# backpower_eeprom_rpibout.net
KiCad netlist of a schematic drawn in EAGLE
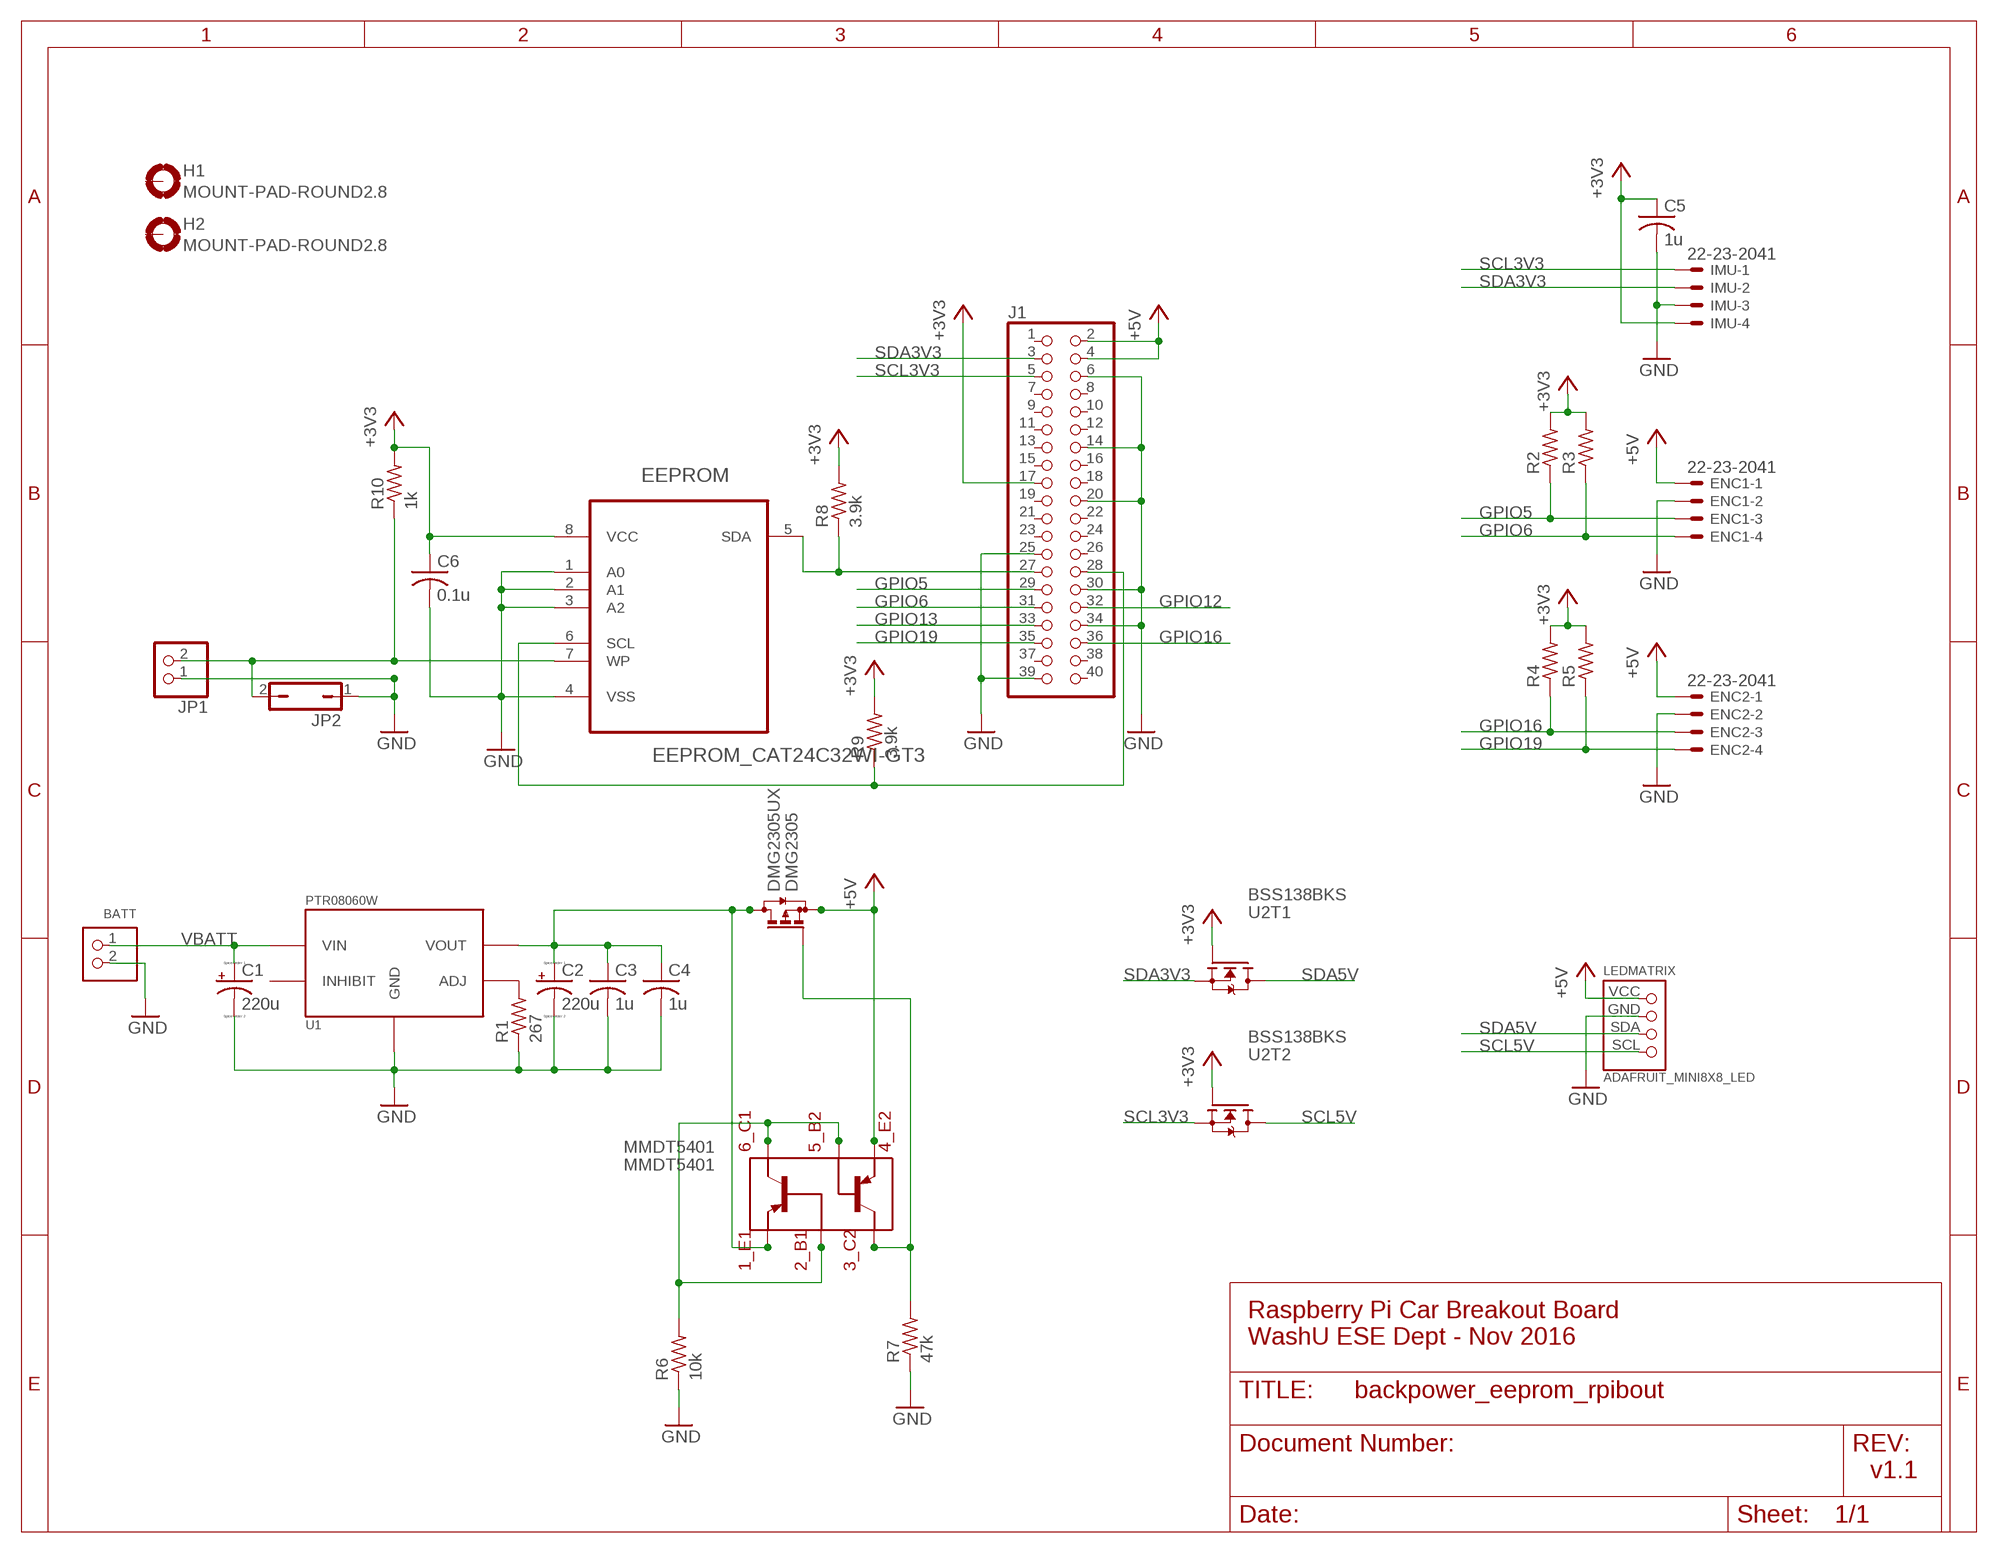
[diagram p0: schematic, sheet 1]

(export (version "E")
  (design (tool "Eeschema 10.0.6"))
  (components
    (comp (ref "BATT")
      (value "ULTRAFIT_2CIRC")
      (footprint "eagle-import:ULTRAFIT_2CIRC_RANGLE")
      (libsource (lib "eagle-import") (part "ULTRAFIT_2CIRC"))
    )
    (comp (ref "C1")
      (value "220u")
      (footprint "eagle-import:E3,5-8")
      (libsource (lib "eagle-import") (part "CPOL-USE3.5-8"))
    )
    (comp (ref "C2")
      (value "220u")
      (footprint "eagle-import:E3,5-8")
      (libsource (lib "eagle-import") (part "CPOL-USE3.5-8"))
    )
    (comp (ref "C3")
      (value "1u")
      (footprint "eagle-import:C1206")
      (libsource (lib "eagle-import") (part "C-USC1206"))
    )
    (comp (ref "C4")
      (value "1u")
      (footprint "eagle-import:C1206")
      (libsource (lib "eagle-import") (part "C-USC1206"))
    )
    (comp (ref "C5")
      (value "1u")
      (footprint "eagle-import:C1206")
      (libsource (lib "eagle-import") (part "C-USC1206"))
    )
    (comp (ref "C6")
      (value "0.1u")
      (footprint "eagle-import:C1206")
      (libsource (lib "eagle-import") (part "C-USC1206"))
    )
    (comp (ref "DMG2305")
      (value "DMG2305UX")
      (footprint "eagle-import:SOT23-3")
      (libsource (lib "eagle-import") (part "DMG2305UX"))
    )
    (comp (ref "EEPROM")
      (value "EEPROM_CAT24C32WI-GT3")
      (footprint "eagle-import:SOIC-8")
      (libsource (lib "eagle-import") (part "EEPROM_CAT24C32WI-GT3"))
    )
    (comp (ref "ENC1")
      (value "22-23-2041")
      (footprint "eagle-import:22-23-2041")
      (fields (field (name "MF") "MOLEX"))
      (libsource (lib "eagle-import") (part "22-23-2041"))
    )
    (comp (ref "ENC2")
      (value "22-23-2041")
      (footprint "eagle-import:22-23-2041")
      (fields (field (name "MF") "MOLEX"))
      (libsource (lib "eagle-import") (part "22-23-2041"))
    )
    (comp (ref "H1")
      (value "MOUNT-PAD-ROUND2.8")
      (footprint "eagle-import:2,8-PAD")
      (libsource (lib "eagle-import") (part "MOUNT-PAD-ROUND2.8"))
    )
    (comp (ref "H2")
      (value "MOUNT-PAD-ROUND2.8")
      (footprint "eagle-import:2,8-PAD")
      (libsource (lib "eagle-import") (part "MOUNT-PAD-ROUND2.8"))
    )
    (comp (ref "IMU")
      (value "22-23-2041")
      (footprint "eagle-import:22-23-2041")
      (fields (field (name "MF") "MOLEX"))
      (libsource (lib "eagle-import") (part "22-23-2041"))
    )
    (comp (ref "J1")
      (value "PINHD-2X20")
      (footprint "eagle-import:2X20")
      (libsource (lib "eagle-import") (part "PINHD-2X20"))
    )
    (comp (ref "JP1")
      (value "PINHD-1X2")
      (footprint "eagle-import:1X02")
      (libsource (lib "eagle-import") (part "PINHD-1X2"))
    )
    (comp (ref "JP2")
      (value "JP1Q")
      (footprint "eagle-import:JP1")
      (libsource (lib "eagle-import") (part "JP1Q"))
    )
    (comp (ref "LEDMATRIX")
      (value "ADAFRUIT_MINI8X8_LED")
      (footprint "eagle-import:ADAFRUIT_MINI8X8_BACKPACK")
      (libsource (lib "eagle-import") (part "ADAFRUIT_MINI8X8_LED"))
    )
    (comp (ref "MMDT5401")
      (value "MMDT5401")
      (footprint "eagle-import:SOT363")
      (libsource (lib "eagle-import") (part "MMDT5401"))
    )
    (comp (ref "R1")
      (value "267")
      (footprint "eagle-import:R1206")
      (libsource (lib "eagle-import") (part "R-US_R1206"))
    )
    (comp (ref "R2")
      (value "R-US_R1206")
      (footprint "eagle-import:R1206")
      (libsource (lib "eagle-import") (part "R-US_R1206"))
    )
    (comp (ref "R3")
      (value "R-US_R1206")
      (footprint "eagle-import:R1206")
      (libsource (lib "eagle-import") (part "R-US_R1206"))
    )
    (comp (ref "R4")
      (value "R-US_R1206")
      (footprint "eagle-import:R1206")
      (libsource (lib "eagle-import") (part "R-US_R1206"))
    )
    (comp (ref "R5")
      (value "R-US_R1206")
      (footprint "eagle-import:R1206")
      (libsource (lib "eagle-import") (part "R-US_R1206"))
    )
    (comp (ref "R6")
      (value "10k")
      (footprint "eagle-import:R1206")
      (libsource (lib "eagle-import") (part "R-US_R1206"))
    )
    (comp (ref "R7")
      (value "47k")
      (footprint "eagle-import:R1206")
      (libsource (lib "eagle-import") (part "R-US_R1206"))
    )
    (comp (ref "R8")
      (value "3.9k")
      (footprint "eagle-import:R1206")
      (libsource (lib "eagle-import") (part "R-US_R1206"))
    )
    (comp (ref "R9")
      (value "3.9k")
      (footprint "eagle-import:R1206")
      (libsource (lib "eagle-import") (part "R-US_R1206"))
    )
    (comp (ref "R10")
      (value "1k")
      (footprint "eagle-import:R1206")
      (libsource (lib "eagle-import") (part "R-US_R1206"))
    )
    (comp (ref "U1")
      (value "PTR08060W")
      (footprint "eagle-import:EDP_MODULE")
      (libsource (lib "eagle-import") (part "PTR08060W"))
    )
    (comp (ref "U2")
      (value "BSS138BKS")
      (footprint "eagle-import:SOT363")
      (libsource (lib "eagle-import") (part "BSS138BKS"))
    )
  )
  (nets
    (net (code "1") (name "+3V3") (class "Default")
      (node (ref "C5") (pin "1") (pinfunction "1_1") (pintype "passive"))
      (node (ref "C6") (pin "1") (pinfunction "1_1") (pintype "passive"))
      (node (ref "EEPROM") (pin "8") (pinfunction "VCC_8") (pintype "power_in"))
      (node (ref "IMU") (pin "4") (pinfunction "S_4") (pintype "passive"))
      (node (ref "J1") (pin "17") (pinfunction "17_17") (pintype "passive"))
      (node (ref "R10") (pin "2") (pinfunction "2_2") (pintype "passive"))
      (node (ref "R2") (pin "2") (pinfunction "2_2") (pintype "passive"))
      (node (ref "R3") (pin "2") (pinfunction "2_2") (pintype "passive"))
      (node (ref "R4") (pin "2") (pinfunction "2_2") (pintype "passive"))
      (node (ref "R5") (pin "2") (pinfunction "2_2") (pintype "passive"))
      (node (ref "R8") (pin "2") (pinfunction "2_2") (pintype "passive"))
      (node (ref "R9") (pin "2") (pinfunction "2_2") (pintype "passive"))
      (node (ref "U2") (pin "2") (pinfunction "G_2") (pintype "passive"))
      (node (ref "U2") (pin "5") (pinfunction "G_5") (pintype "passive"))
    )
    (net (code "2") (name "+5V") (class "Default")
      (node (ref "DMG2305") (pin "2") (pinfunction "S_2") (pintype "passive"))
      (node (ref "ENC1") (pin "1") (pinfunction "S_1") (pintype "passive"))
      (node (ref "ENC2") (pin "1") (pinfunction "S_1") (pintype "passive"))
      (node (ref "J1") (pin "2") (pinfunction "2_2") (pintype "passive"))
      (node (ref "J1") (pin "4") (pinfunction "4_4") (pintype "passive"))
      (node (ref "LEDMATRIX") (pin "VCC") (pinfunction "VCC_VCC") (pintype "power_in"))
      (node (ref "MMDT5401") (pin "1") (pinfunction "E1_1") (pintype "passive"))
    )
    (net (code "3") (name "/GPIO5") (class "Default")
      (node (ref "ENC1") (pin "3") (pinfunction "S_3") (pintype "passive"))
      (node (ref "J1") (pin "29") (pinfunction "29_29") (pintype "passive"))
      (node (ref "R2") (pin "1") (pinfunction "1_1") (pintype "passive"))
    )
    (net (code "4") (name "/GPIO6") (class "Default")
      (node (ref "ENC1") (pin "4") (pinfunction "S_4") (pintype "passive"))
      (node (ref "J1") (pin "31") (pinfunction "31_31") (pintype "passive"))
      (node (ref "R3") (pin "1") (pinfunction "1_1") (pintype "passive"))
    )
    (net (code "5") (name "/GPIO12") (class "Default")
      (node (ref "J1") (pin "32") (pinfunction "32_32") (pintype "passive"))
    )
    (net (code "6") (name "/GPIO13") (class "Default")
      (node (ref "J1") (pin "33") (pinfunction "33_33") (pintype "passive"))
    )
    (net (code "7") (name "/GPIO16") (class "Default")
      (node (ref "ENC2") (pin "3") (pinfunction "S_3") (pintype "passive"))
      (node (ref "J1") (pin "36") (pinfunction "36_36") (pintype "passive"))
      (node (ref "R4") (pin "1") (pinfunction "1_1") (pintype "passive"))
    )
    (net (code "8") (name "/GPIO19") (class "Default")
      (node (ref "ENC2") (pin "4") (pinfunction "S_4") (pintype "passive"))
      (node (ref "J1") (pin "35") (pinfunction "35_35") (pintype "passive"))
      (node (ref "R5") (pin "1") (pinfunction "1_1") (pintype "passive"))
    )
    (net (code "9") (name "/SCL3V3") (class "Default")
      (node (ref "IMU") (pin "1") (pinfunction "S_1") (pintype "passive"))
      (node (ref "J1") (pin "5") (pinfunction "5_5") (pintype "passive"))
      (node (ref "U2") (pin "4") (pinfunction "S_4") (pintype "passive"))
    )
    (net (code "10") (name "/SCL5V") (class "Default")
      (node (ref "LEDMATRIX") (pin "SCL") (pinfunction "SCL_SCL") (pintype "bidirectional"))
      (node (ref "U2") (pin "3") (pinfunction "D_3") (pintype "passive"))
    )
    (net (code "11") (name "/SDA3V3") (class "Default")
      (node (ref "IMU") (pin "2") (pinfunction "S_2") (pintype "passive"))
      (node (ref "J1") (pin "3") (pinfunction "3_3") (pintype "passive"))
      (node (ref "U2") (pin "1") (pinfunction "S_1") (pintype "passive"))
    )
    (net (code "12") (name "/SDA5V") (class "Default")
      (node (ref "LEDMATRIX") (pin "SDA") (pinfunction "SDA_SDA") (pintype "bidirectional"))
      (node (ref "U2") (pin "6") (pinfunction "D_6") (pintype "passive"))
    )
    (net (code "13") (name "/VBATT") (class "Default")
      (node (ref "BATT") (pin "1") (pinfunction "P1_1") (pintype "power_in"))
      (node (ref "C1") (pin "+") (pinfunction "+_+") (pintype "passive"))
      (node (ref "U1") (pin "P2") (pinfunction "VIN_P2") (pintype "power_in"))
    )
    (net (code "14") (name "GND") (class "Default")
      (node (ref "BATT") (pin "2") (pinfunction "P2_2") (pintype "power_in"))
      (node (ref "C1") (pin "-") (pinfunction "-_-") (pintype "passive"))
      (node (ref "C2") (pin "-") (pinfunction "-_-") (pintype "passive"))
      (node (ref "C3") (pin "2") (pinfunction "2_2") (pintype "passive"))
      (node (ref "C4") (pin "2") (pinfunction "2_2") (pintype "passive"))
      (node (ref "C5") (pin "2") (pinfunction "2_2") (pintype "passive"))
      (node (ref "C6") (pin "2") (pinfunction "2_2") (pintype "passive"))
      (node (ref "EEPROM") (pin "1") (pinfunction "A0_1") (pintype "input"))
      (node (ref "EEPROM") (pin "2") (pinfunction "A1_2") (pintype "input"))
      (node (ref "EEPROM") (pin "3") (pinfunction "A2_3") (pintype "input"))
      (node (ref "EEPROM") (pin "4") (pinfunction "VSS_4") (pintype "passive"))
      (node (ref "ENC1") (pin "2") (pinfunction "S_2") (pintype "passive"))
      (node (ref "ENC2") (pin "2") (pinfunction "S_2") (pintype "passive"))
      (node (ref "IMU") (pin "3") (pinfunction "S_3") (pintype "passive"))
      (node (ref "J1") (pin "14") (pinfunction "14_14") (pintype "passive"))
      (node (ref "J1") (pin "20") (pinfunction "20_20") (pintype "passive"))
      (node (ref "J1") (pin "25") (pinfunction "25_25") (pintype "passive"))
      (node (ref "J1") (pin "30") (pinfunction "30_30") (pintype "passive"))
      (node (ref "J1") (pin "34") (pinfunction "34_34") (pintype "passive"))
      (node (ref "J1") (pin "39") (pinfunction "39_39") (pintype "passive"))
      (node (ref "J1") (pin "6") (pinfunction "6_6") (pintype "passive"))
      (node (ref "JP1") (pin "1") (pinfunction "1_1") (pintype "passive"))
      (node (ref "JP2") (pin "1") (pinfunction "1_1") (pintype "passive"))
      (node (ref "LEDMATRIX") (pin "GND") (pinfunction "GND_GND") (pintype "power_in"))
      (node (ref "R1") (pin "1") (pinfunction "1_1") (pintype "passive"))
      (node (ref "R6") (pin "1") (pinfunction "1_1") (pintype "passive"))
      (node (ref "R7") (pin "1") (pinfunction "1_1") (pintype "passive"))
      (node (ref "U1") (pin "P3") (pinfunction "GND_P3") (pintype "power_in"))
    )
    (net (code "15") (name "Net-(DMG2305-D)") (class "Default")
      (node (ref "C2") (pin "+") (pinfunction "+_+") (pintype "passive"))
      (node (ref "C3") (pin "1") (pinfunction "1_1") (pintype "passive"))
      (node (ref "C4") (pin "1") (pinfunction "1_1") (pintype "passive"))
      (node (ref "DMG2305") (pin "3") (pinfunction "D_3") (pintype "passive"))
      (node (ref "MMDT5401") (pin "4") (pinfunction "E2_4") (pintype "passive"))
      (node (ref "U1") (pin "P4") (pinfunction "VOUT_P4") (pintype "power_in"))
    )
    (net (code "16") (name "Net-(DMG2305-G)") (class "Default")
      (node (ref "DMG2305") (pin "1") (pinfunction "G_1") (pintype "passive"))
      (node (ref "MMDT5401") (pin "6") (pinfunction "C1_6") (pintype "passive"))
      (node (ref "R7") (pin "2") (pinfunction "2_2") (pintype "passive"))
    )
    (net (code "17") (name "Net-(EEPROM-SCL)") (class "Default")
      (node (ref "EEPROM") (pin "6") (pinfunction "SCL_6") (pintype "input"))
      (node (ref "J1") (pin "28") (pinfunction "28_28") (pintype "passive"))
      (node (ref "R9") (pin "1") (pinfunction "1_1") (pintype "passive"))
    )
    (net (code "18") (name "Net-(EEPROM-SDA)") (class "Default")
      (node (ref "EEPROM") (pin "5") (pinfunction "SDA_5") (pintype "bidirectional"))
      (node (ref "J1") (pin "27") (pinfunction "27_27") (pintype "passive"))
      (node (ref "R8") (pin "1") (pinfunction "1_1") (pintype "passive"))
    )
    (net (code "19") (name "Net-(EEPROM-WP)") (class "Default")
      (node (ref "EEPROM") (pin "7") (pinfunction "WP_7") (pintype "input"))
      (node (ref "JP1") (pin "2") (pinfunction "2_2") (pintype "passive"))
      (node (ref "JP2") (pin "2") (pinfunction "2_2") (pintype "passive"))
      (node (ref "R10") (pin "1") (pinfunction "1_1") (pintype "passive"))
    )
    (net (code "20") (name "Net-(MMDT5401-B1)") (class "Default")
      (node (ref "MMDT5401") (pin "2") (pinfunction "B1_2") (pintype "passive"))
      (node (ref "MMDT5401") (pin "3") (pinfunction "C2_3") (pintype "passive"))
      (node (ref "MMDT5401") (pin "5") (pinfunction "B2_5") (pintype "passive"))
      (node (ref "R6") (pin "2") (pinfunction "2_2") (pintype "passive"))
    )
    (net (code "21") (name "Net-(U1-ADJ)") (class "Default")
      (node (ref "R1") (pin "2") (pinfunction "2_2") (pintype "passive"))
      (node (ref "U1") (pin "P5") (pinfunction "ADJ_P5") (pintype "passive"))
    )
    (net (code "22") (name "unconnected-(H1-MOUNT-PadB2,8)") (class "Default")
      (node (ref "H1") (pin "B2,8") (pinfunction "MOUNT_B2,8") (pintype "passive"))
    )
    (net (code "23") (name "unconnected-(H2-MOUNT-PadB2,8)") (class "Default")
      (node (ref "H2") (pin "B2,8") (pinfunction "MOUNT_B2,8") (pintype "passive"))
    )
    (net (code "24") (name "unconnected-(J1-Pad1)") (class "Default")
      (node (ref "J1") (pin "1") (pinfunction "1_1") (pintype "passive"))
    )
    (net (code "25") (name "unconnected-(J1-Pad7)") (class "Default")
      (node (ref "J1") (pin "7") (pinfunction "7_7") (pintype "passive"))
    )
    (net (code "26") (name "unconnected-(J1-Pad8)") (class "Default")
      (node (ref "J1") (pin "8") (pinfunction "8_8") (pintype "passive"))
    )
    (net (code "27") (name "unconnected-(J1-Pad9)") (class "Default")
      (node (ref "J1") (pin "9") (pinfunction "9_9") (pintype "passive"))
    )
    (net (code "28") (name "unconnected-(J1-Pad10)") (class "Default")
      (node (ref "J1") (pin "10") (pinfunction "10_10") (pintype "passive"))
    )
    (net (code "29") (name "unconnected-(J1-Pad11)") (class "Default")
      (node (ref "J1") (pin "11") (pinfunction "11_11") (pintype "passive"))
    )
    (net (code "30") (name "unconnected-(J1-Pad12)") (class "Default")
      (node (ref "J1") (pin "12") (pinfunction "12_12") (pintype "passive"))
    )
    (net (code "31") (name "unconnected-(J1-Pad13)") (class "Default")
      (node (ref "J1") (pin "13") (pinfunction "13_13") (pintype "passive"))
    )
    (net (code "32") (name "unconnected-(J1-Pad15)") (class "Default")
      (node (ref "J1") (pin "15") (pinfunction "15_15") (pintype "passive"))
    )
    (net (code "33") (name "unconnected-(J1-Pad16)") (class "Default")
      (node (ref "J1") (pin "16") (pinfunction "16_16") (pintype "passive"))
    )
    (net (code "34") (name "unconnected-(J1-Pad18)") (class "Default")
      (node (ref "J1") (pin "18") (pinfunction "18_18") (pintype "passive"))
    )
    (net (code "35") (name "unconnected-(J1-Pad19)") (class "Default")
      (node (ref "J1") (pin "19") (pinfunction "19_19") (pintype "passive"))
    )
    (net (code "36") (name "unconnected-(J1-Pad21)") (class "Default")
      (node (ref "J1") (pin "21") (pinfunction "21_21") (pintype "passive"))
    )
    (net (code "37") (name "unconnected-(J1-Pad22)") (class "Default")
      (node (ref "J1") (pin "22") (pinfunction "22_22") (pintype "passive"))
    )
    (net (code "38") (name "unconnected-(J1-Pad23)") (class "Default")
      (node (ref "J1") (pin "23") (pinfunction "23_23") (pintype "passive"))
    )
    (net (code "39") (name "unconnected-(J1-Pad24)") (class "Default")
      (node (ref "J1") (pin "24") (pinfunction "24_24") (pintype "passive"))
    )
    (net (code "40") (name "unconnected-(J1-Pad26)") (class "Default")
      (node (ref "J1") (pin "26") (pinfunction "26_26") (pintype "passive"))
    )
    (net (code "41") (name "unconnected-(J1-Pad37)") (class "Default")
      (node (ref "J1") (pin "37") (pinfunction "37_37") (pintype "passive"))
    )
    (net (code "42") (name "unconnected-(J1-Pad38)") (class "Default")
      (node (ref "J1") (pin "38") (pinfunction "38_38") (pintype "passive"))
    )
    (net (code "43") (name "unconnected-(J1-Pad40)") (class "Default")
      (node (ref "J1") (pin "40") (pinfunction "40_40") (pintype "passive"))
    )
    (net (code "44") (name "unconnected-(U1-INHIBIT-PadP1)") (class "Default")
      (node (ref "U1") (pin "P1") (pinfunction "INHIBIT_P1") (pintype "open_collector"))
    )
  )
)
